# SCH_TESIS_2025-09-22.net
KiCad netlist of a schematic drawn in EasyEDA
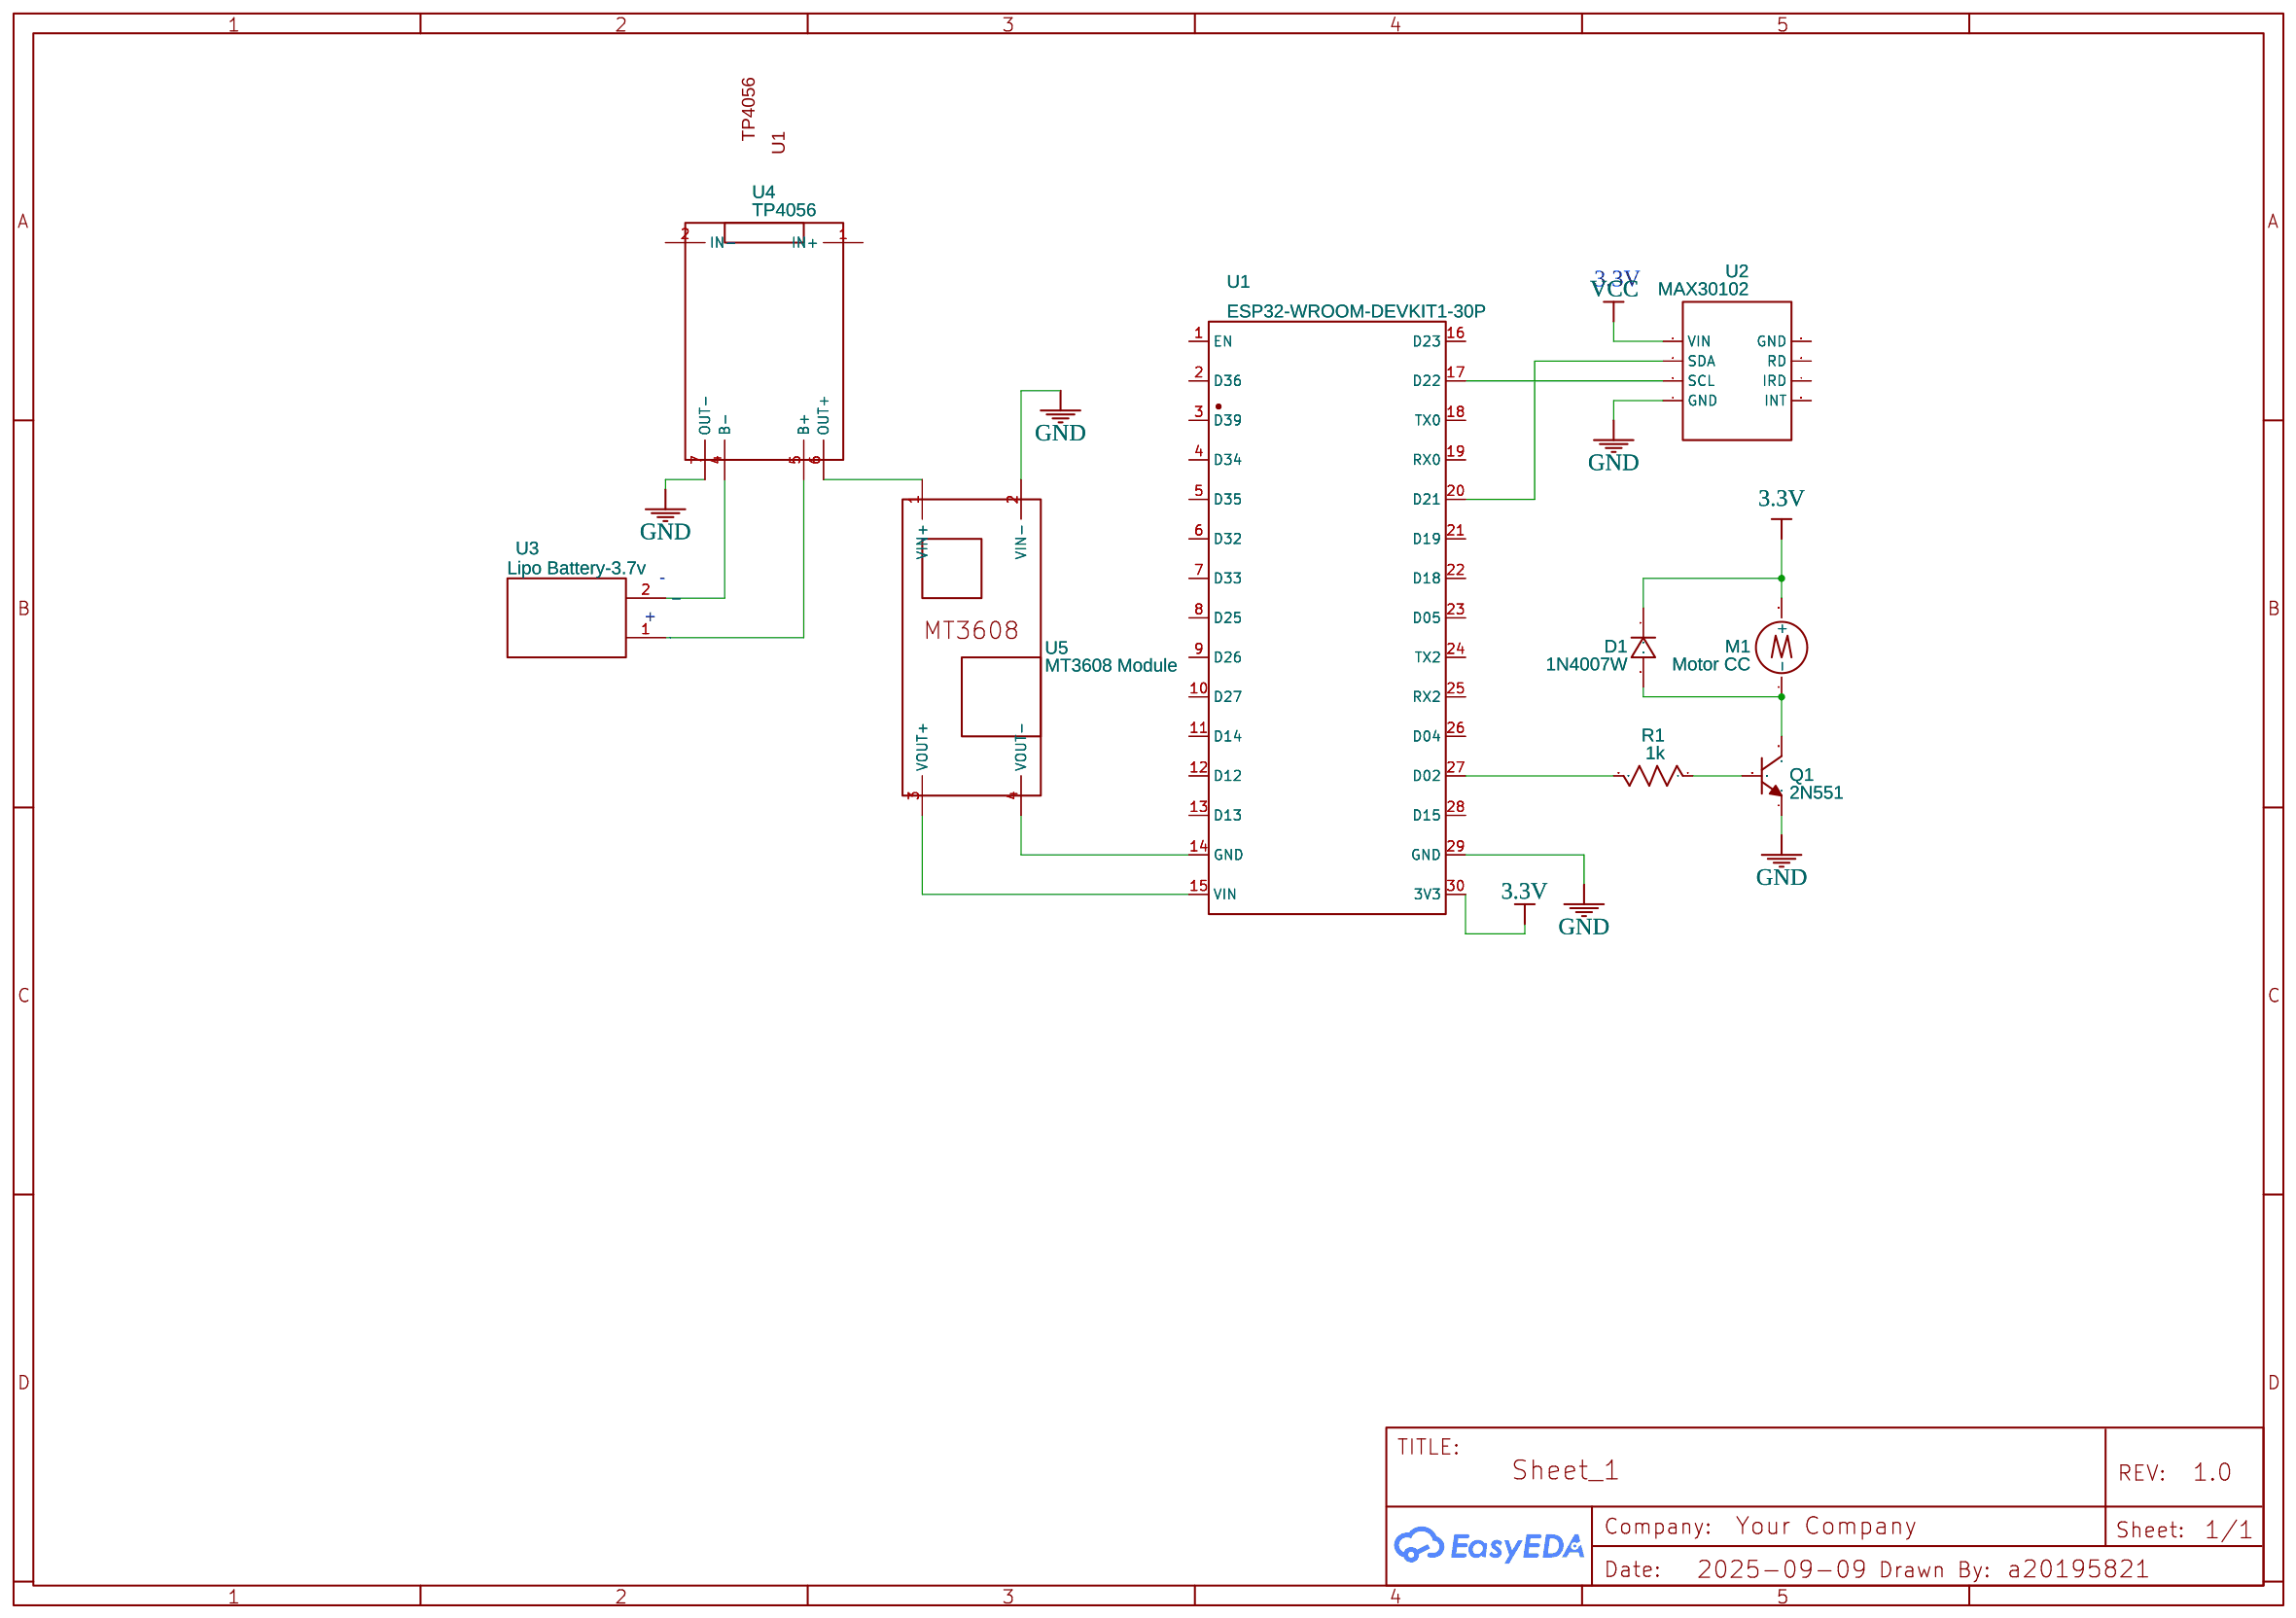
[diagram p0: schematic sheet]

(export (version "E")
  (design (tool "Eeschema 10.0.6"))
  (components
    (comp (ref "D1")
      (value "1N4007W")
      (fields (field (name "Manufacturer") "BLUE ROCKET"))
      (libsource (lib "") (part "1N4007W"))
    )
    (comp (ref "M1") (value "Motor CC") (libsource (lib "") (part "Motor CC")))
    (comp (ref "Q1") (value "2N551") (libsource (lib "") (part "2N551")))
    (comp (ref "R1") (value "1k") (libsource (lib "") (part "R_0603_US")))
    (comp (ref "U1") (value "ESP32-WROOM-DEVKIT1-30P") (libsource (lib "") (part "ESP32-WROOM-DEVKIT1-30P")))
    (comp (ref "U2") (value "MAX30102") (libsource (lib "") (part "MAX30102")))
    (comp (ref "U3") (value "Lipo Battery-3.7v") (libsource (lib "") (part "Lipo Battery-3.7v")))
    (comp (ref "U4") (value "TP4056") (libsource (lib "") (part "TP4056")))
    (comp (ref "U5") (value "MT3608 Module") (libsource (lib "") (part "MT3608 Module")))
  )
  (nets
    (net (code "1") (name "3.3V") (class "Default")
      (node (ref "D1") (pin "1") (pinfunction "1_1") (pintype "unspecified"))
      (node (ref "M1") (pin "2") (pinfunction "+_2") (pintype "unspecified"))
      (node (ref "U1") (pin "30") (pinfunction "3V3_30") (pintype "unspecified"))
    )
    (net (code "2") (name "GND") (class "Default")
      (node (ref "Q1") (pin "E") (pinfunction "E_E") (pintype "unspecified"))
      (node (ref "U1") (pin "29") (pinfunction "GND_29") (pintype "unspecified"))
      (node (ref "U2") (pin "4") (pinfunction "GND_4") (pintype "unspecified"))
      (node (ref "U4") (pin "7") (pinfunction "OUT-_7") (pintype "unspecified"))
      (node (ref "U5") (pin "2") (pinfunction "VIN-_2") (pintype "unspecified"))
    )
    (net (code "3") (name "Net-(M1--)") (class "Default")
      (node (ref "D1") (pin "2") (pinfunction "2_2") (pintype "unspecified"))
      (node (ref "M1") (pin "1") (pinfunction "-_1") (pintype "unspecified"))
      (node (ref "Q1") (pin "C") (pinfunction "C_C") (pintype "unspecified"))
    )
    (net (code "4") (name "Net-(Q1-PadB)") (class "Default")
      (node (ref "Q1") (pin "B") (pinfunction "B_B") (pintype "unspecified"))
      (node (ref "R1") (pin "1") (pinfunction "1_1") (pintype "unspecified"))
    )
    (net (code "5") (name "Net-(U1-D02)") (class "Default")
      (node (ref "R1") (pin "2") (pinfunction "2_2") (pintype "unspecified"))
      (node (ref "U1") (pin "27") (pinfunction "D02_27") (pintype "unspecified"))
    )
    (net (code "6") (name "Net-(U1-D21)") (class "Default")
      (node (ref "U1") (pin "20") (pinfunction "D21_20") (pintype "unspecified"))
      (node (ref "U2") (pin "2") (pinfunction "SDA_2") (pintype "unspecified"))
    )
    (net (code "7") (name "Net-(U1-D22)") (class "Default")
      (node (ref "U1") (pin "17") (pinfunction "D22_17") (pintype "unspecified"))
      (node (ref "U2") (pin "3") (pinfunction "SCL_3") (pintype "unspecified"))
    )
    (net (code "8") (name "Net-(U1-VIN)") (class "Default")
      (node (ref "U1") (pin "15") (pinfunction "VIN_15") (pintype "unspecified"))
      (node (ref "U5") (pin "3") (pinfunction "VOUT+_3") (pintype "unspecified"))
    )
    (net (code "9") (name "Net-(U4-OUT+)") (class "Default")
      (node (ref "U4") (pin "6") (pinfunction "OUT+_6") (pintype "unspecified"))
      (node (ref "U5") (pin "1") (pinfunction "VIN+_1") (pintype "unspecified"))
    )
    (net (code "10") (name "Net-(U5-VOUT-)") (class "Default")
      (node (ref "U1") (pin "14") (pinfunction "GND_14") (pintype "unspecified"))
      (node (ref "U5") (pin "4") (pinfunction "VOUT-_4") (pintype "unspecified"))
    )
    (net (code "11") (name "VCC") (class "Default")
      (node (ref "U2") (pin "1") (pinfunction "VIN_1") (pintype "unspecified"))
    )
    (net (code "12") (name "unconnected-(U1-D04-Pad26)") (class "Default")
      (node (ref "U1") (pin "26") (pinfunction "D04_26") (pintype "unspecified"))
    )
    (net (code "13") (name "unconnected-(U1-D05-Pad23)") (class "Default")
      (node (ref "U1") (pin "23") (pinfunction "D05_23") (pintype "unspecified"))
    )
    (net (code "14") (name "unconnected-(U1-D12-Pad12)") (class "Default")
      (node (ref "U1") (pin "12") (pinfunction "D12_12") (pintype "unspecified"))
    )
    (net (code "15") (name "unconnected-(U1-D13-Pad13)") (class "Default")
      (node (ref "U1") (pin "13") (pinfunction "D13_13") (pintype "unspecified"))
    )
    (net (code "16") (name "unconnected-(U1-D14-Pad11)") (class "Default")
      (node (ref "U1") (pin "11") (pinfunction "D14_11") (pintype "unspecified"))
    )
    (net (code "17") (name "unconnected-(U1-D15-Pad28)") (class "Default")
      (node (ref "U1") (pin "28") (pinfunction "D15_28") (pintype "unspecified"))
    )
    (net (code "18") (name "unconnected-(U1-D18-Pad22)") (class "Default")
      (node (ref "U1") (pin "22") (pinfunction "D18_22") (pintype "unspecified"))
    )
    (net (code "19") (name "unconnected-(U1-D19-Pad21)") (class "Default")
      (node (ref "U1") (pin "21") (pinfunction "D19_21") (pintype "unspecified"))
    )
    (net (code "20") (name "unconnected-(U1-D23-Pad16)") (class "Default")
      (node (ref "U1") (pin "16") (pinfunction "D23_16") (pintype "unspecified"))
    )
    (net (code "21") (name "unconnected-(U1-D25-Pad8)") (class "Default")
      (node (ref "U1") (pin "8") (pinfunction "D25_8") (pintype "unspecified"))
    )
    (net (code "22") (name "unconnected-(U1-D26-Pad9)") (class "Default")
      (node (ref "U1") (pin "9") (pinfunction "D26_9") (pintype "unspecified"))
    )
    (net (code "23") (name "unconnected-(U1-D27-Pad10)") (class "Default")
      (node (ref "U1") (pin "10") (pinfunction "D27_10") (pintype "unspecified"))
    )
    (net (code "24") (name "unconnected-(U1-D32-Pad6)") (class "Default")
      (node (ref "U1") (pin "6") (pinfunction "D32_6") (pintype "unspecified"))
    )
    (net (code "25") (name "unconnected-(U1-D33-Pad7)") (class "Default")
      (node (ref "U1") (pin "7") (pinfunction "D33_7") (pintype "unspecified"))
    )
    (net (code "26") (name "unconnected-(U1-D34-Pad4)") (class "Default")
      (node (ref "U1") (pin "4") (pinfunction "D34_4") (pintype "unspecified"))
    )
    (net (code "27") (name "unconnected-(U1-D35-Pad5)") (class "Default")
      (node (ref "U1") (pin "5") (pinfunction "D35_5") (pintype "unspecified"))
    )
    (net (code "28") (name "unconnected-(U1-D36-Pad2)") (class "Default")
      (node (ref "U1") (pin "2") (pinfunction "D36_2") (pintype "unspecified"))
    )
    (net (code "29") (name "unconnected-(U1-D39-Pad3)") (class "Default")
      (node (ref "U1") (pin "3") (pinfunction "D39_3") (pintype "unspecified"))
    )
    (net (code "30") (name "unconnected-(U1-EN-Pad1)") (class "Default")
      (node (ref "U1") (pin "1") (pinfunction "EN_1") (pintype "unspecified"))
    )
    (net (code "31") (name "unconnected-(U1-RX0-Pad19)") (class "Default")
      (node (ref "U1") (pin "19") (pinfunction "RX0_19") (pintype "unspecified"))
    )
    (net (code "32") (name "unconnected-(U1-RX2-Pad25)") (class "Default")
      (node (ref "U1") (pin "25") (pinfunction "RX2_25") (pintype "unspecified"))
    )
    (net (code "33") (name "unconnected-(U1-TX0-Pad18)") (class "Default")
      (node (ref "U1") (pin "18") (pinfunction "TX0_18") (pintype "unspecified"))
    )
    (net (code "34") (name "unconnected-(U1-TX2-Pad24)") (class "Default")
      (node (ref "U1") (pin "24") (pinfunction "TX2_24") (pintype "unspecified"))
    )
    (net (code "35") (name "unconnected-(U2-GND-Pad5)") (class "Default")
      (node (ref "U2") (pin "5") (pinfunction "GND_5") (pintype "unspecified"))
    )
    (net (code "36") (name "unconnected-(U2-INT-Pad8)") (class "Default")
      (node (ref "U2") (pin "8") (pinfunction "INT_8") (pintype "unspecified"))
    )
    (net (code "37") (name "unconnected-(U2-IRD-Pad7)") (class "Default")
      (node (ref "U2") (pin "7") (pinfunction "IRD_7") (pintype "unspecified"))
    )
    (net (code "38") (name "unconnected-(U2-RD-Pad6)") (class "Default")
      (node (ref "U2") (pin "6") (pinfunction "RD_6") (pintype "unspecified"))
    )
    (net (code "39") (name "unconnected-(U3-+-Pad1)") (class "Default")
      (node (ref "U3") (pin "1") (pinfunction "+_1") (pintype "unspecified"))
    )
    (net (code "40") (name "unconnected-(U3---Pad2)") (class "Default")
      (node (ref "U3") (pin "2") (pinfunction "-_2") (pintype "unspecified"))
    )
    (net (code "41") (name "unconnected-(U4-B+-Pad5)") (class "Default")
      (node (ref "U4") (pin "5") (pinfunction "B+_5") (pintype "unspecified"))
    )
    (net (code "42") (name "unconnected-(U4-B--Pad4)") (class "Default")
      (node (ref "U4") (pin "4") (pinfunction "B-_4") (pintype "unspecified"))
    )
    (net (code "43") (name "unconnected-(U4-IN+-Pad1)") (class "Default")
      (node (ref "U4") (pin "1") (pinfunction "IN+_1") (pintype "unspecified"))
    )
    (net (code "44") (name "unconnected-(U4-IN--Pad2)") (class "Default")
      (node (ref "U4") (pin "2") (pinfunction "IN-_2") (pintype "unspecified"))
    )
  )
)
